# bypass.net
KiCad netlist of a schematic drawn in EAGLE
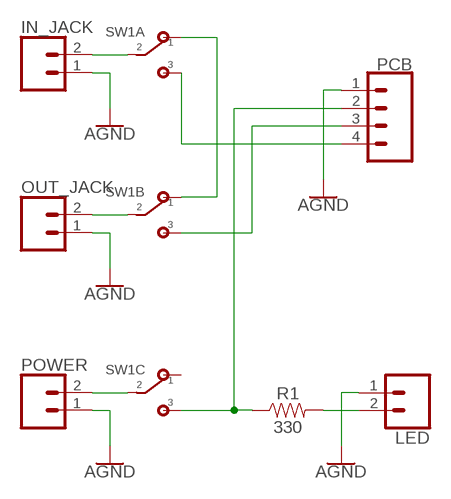
[diagram p0: schematic, sheet 1]

(export (version "E")
  (design (tool "Eeschema 10.0.6"))
  (components
    (comp (ref "IN_JACK")
      (value "CONN_02POLAR")
      (footprint "eagle-import:MOLEX-1X2")
      (libsource (lib "eagle-import") (part "CONN_02POLAR"))
    )
    (comp (ref "LED")
      (value "CONN_02POLAR")
      (footprint "eagle-import:MOLEX-1X2")
      (libsource (lib "eagle-import") (part "CONN_02POLAR"))
    )
    (comp (ref "OUT_JACK")
      (value "CONN_02POLAR")
      (footprint "eagle-import:MOLEX-1X2")
      (libsource (lib "eagle-import") (part "CONN_02POLAR"))
    )
    (comp (ref "PCB")
      (value "PCB-INOUTPOLAR")
      (footprint "eagle-import:MOLEX-1X4")
      (libsource (lib "eagle-import") (part "PCB-INOUTPOLAR"))
    )
    (comp (ref "POWER")
      (value "CONN_02POLAR")
      (footprint "eagle-import:MOLEX-1X2")
      (libsource (lib "eagle-import") (part "CONN_02POLAR"))
    )
    (comp (ref "R1")
      (value "330")
      (footprint "eagle-import:AXIAL-0.3")
      (libsource (lib "eagle-import") (part "330OHM-HORIZ-1/10W-5%"))
    )
    (comp (ref "SW1")
      (value "3PDT")
      (footprint "eagle-import:3PDT")
      (libsource (lib "eagle-import") (part "3PDT"))
    )
  )
  (nets
    (net (code "1") (name "AGND") (class "Default")
      (node (ref "IN_JACK") (pin "1") (pinfunction "1_1") (pintype "passive"))
      (node (ref "LED") (pin "1") (pinfunction "1_1") (pintype "passive"))
      (node (ref "OUT_JACK") (pin "1") (pinfunction "1_1") (pintype "passive"))
      (node (ref "PCB") (pin "1") (pinfunction "1_1") (pintype "passive"))
      (node (ref "POWER") (pin "1") (pinfunction "1_1") (pintype "passive"))
    )
    (net (code "2") (name "Net-(R1-1)") (class "Default")
      (node (ref "PCB") (pin "2") (pinfunction "2_2") (pintype "passive"))
      (node (ref "R1") (pin "P$1") (pinfunction "1_P$1") (pintype "passive"))
      (node (ref "SW1") (pin "C3") (pinfunction "P$3_C3") (pintype "bidirectional"))
    )
    (net (code "3") (name "Net-(R1-2)") (class "Default")
      (node (ref "LED") (pin "2") (pinfunction "2_2") (pintype "passive"))
      (node (ref "R1") (pin "P$2") (pinfunction "2_P$2") (pintype "passive"))
    )
    (net (code "4") (name "Net-(SW1A-P$1)") (class "Default")
      (node (ref "SW1") (pin "A1") (pinfunction "P$1_A1") (pintype "bidirectional"))
      (node (ref "SW1") (pin "B1") (pinfunction "P$1_B1") (pintype "bidirectional"))
    )
    (net (code "5") (name "Net-(SW1A-P$2)") (class "Default")
      (node (ref "IN_JACK") (pin "2") (pinfunction "2_2") (pintype "passive"))
      (node (ref "SW1") (pin "A2") (pinfunction "P$2_A2") (pintype "bidirectional"))
    )
    (net (code "6") (name "Net-(SW1A-P$3)") (class "Default")
      (node (ref "PCB") (pin "4") (pinfunction "4_4") (pintype "passive"))
      (node (ref "SW1") (pin "A3") (pinfunction "P$3_A3") (pintype "bidirectional"))
    )
    (net (code "7") (name "Net-(SW1B-P$2)") (class "Default")
      (node (ref "OUT_JACK") (pin "2") (pinfunction "2_2") (pintype "passive"))
      (node (ref "SW1") (pin "B2") (pinfunction "P$2_B2") (pintype "bidirectional"))
    )
    (net (code "8") (name "Net-(SW1B-P$3)") (class "Default")
      (node (ref "PCB") (pin "3") (pinfunction "3_3") (pintype "passive"))
      (node (ref "SW1") (pin "B3") (pinfunction "P$3_B3") (pintype "bidirectional"))
    )
    (net (code "9") (name "Net-(SW1C-P$2)") (class "Default")
      (node (ref "POWER") (pin "2") (pinfunction "2_2") (pintype "passive"))
      (node (ref "SW1") (pin "C2") (pinfunction "P$2_C2") (pintype "bidirectional"))
    )
    (net (code "10") (name "unconnected-(SW1C-P$1-PadC1)") (class "Default")
      (node (ref "SW1") (pin "C1") (pinfunction "P$1_C1") (pintype "bidirectional"))
    )
  )
)
